# WC_Adaptor.net
KiCad netlist of a schematic drawn in EAGLE
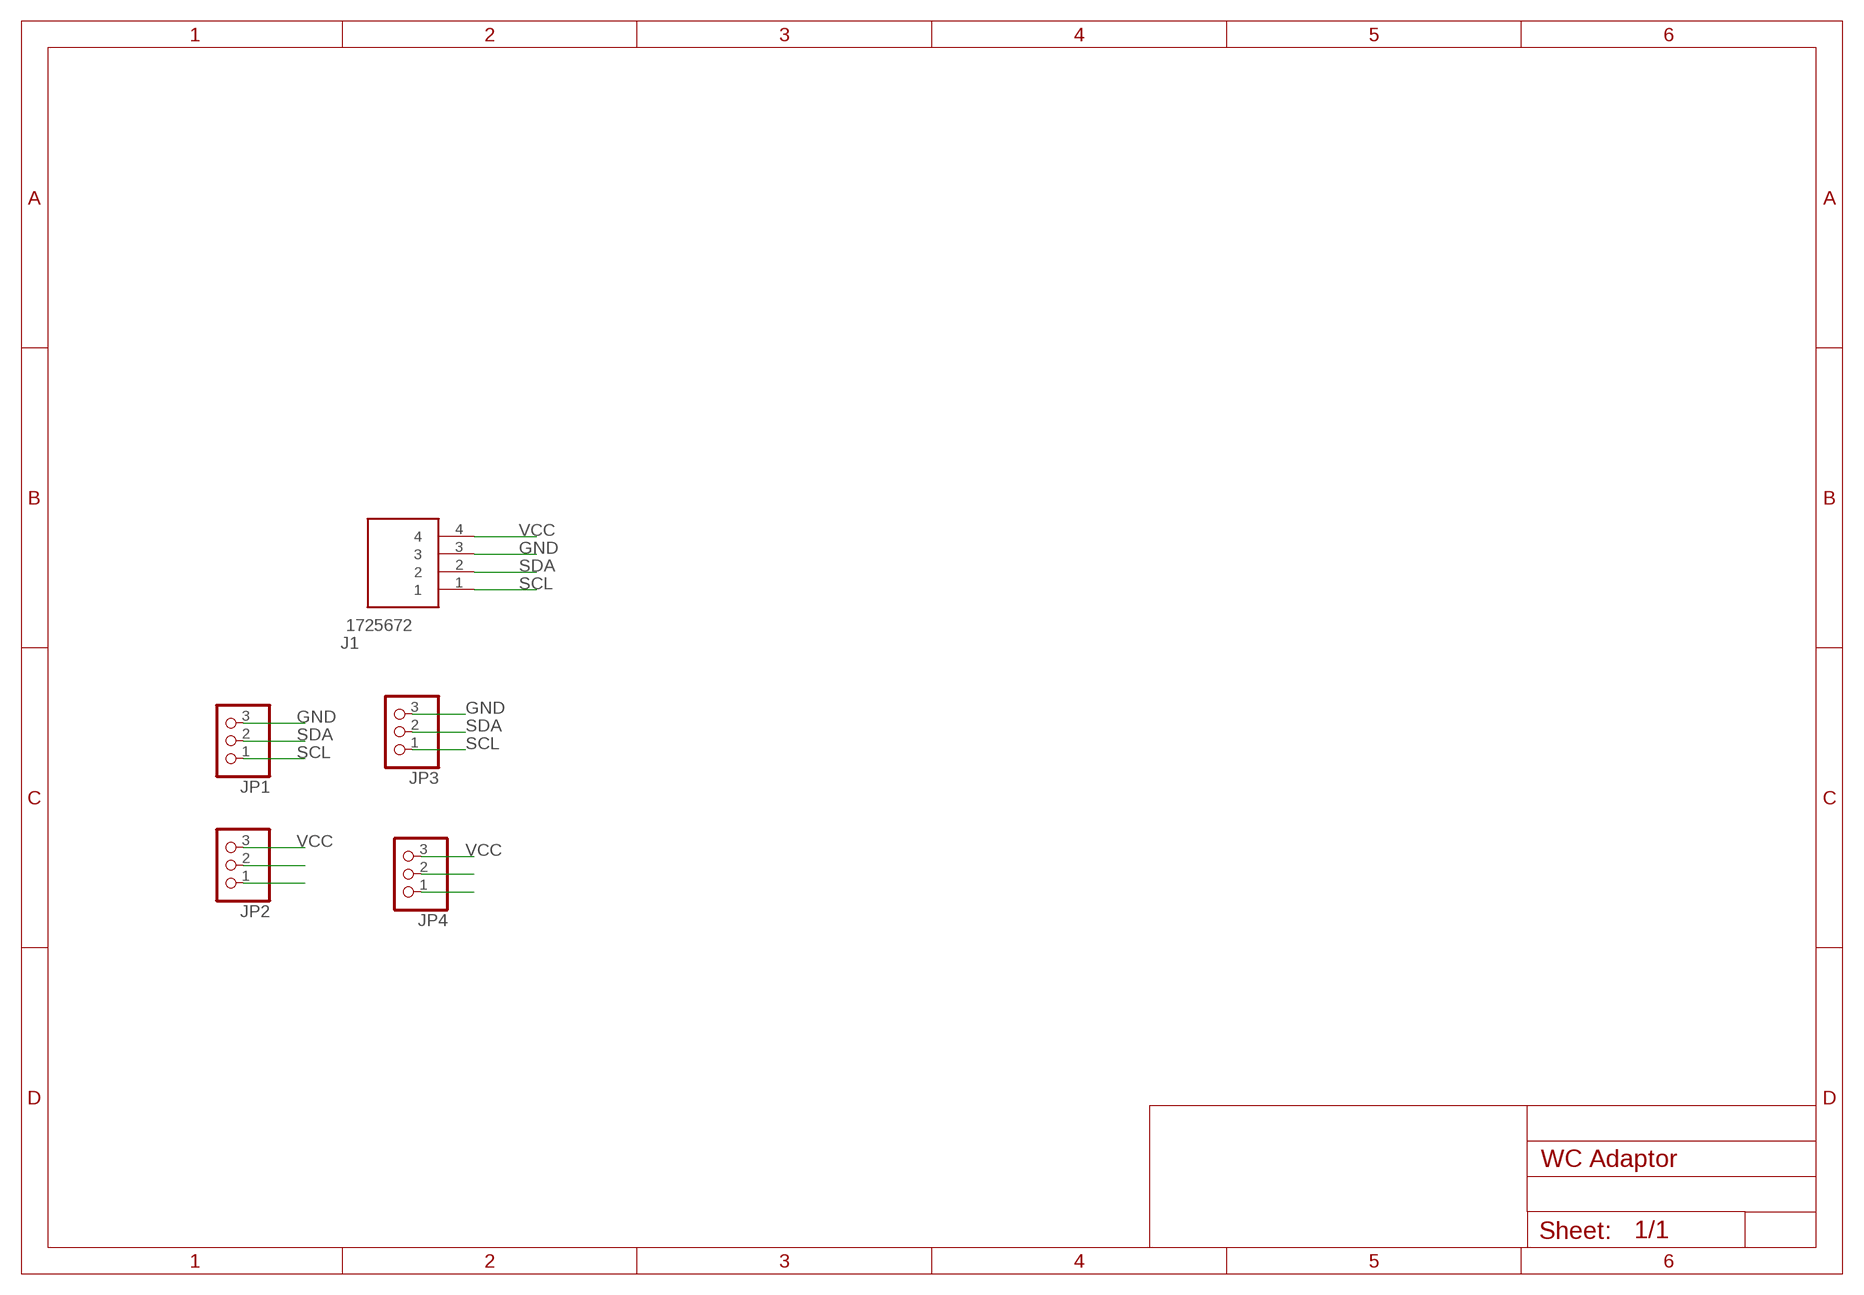
[diagram p0: schematic, sheet 1]

(export (version "E")
  (design (tool "Eeschema 10.0.6"))
  (components
    (comp (ref "J1")
      (value "1725672")
      (footprint "eagle-import:1725672")
      (fields (field (name "MOUSER_PART_NUMBER") "651-1725672"))
      (libsource (lib "eagle-import") (part "1725672"))
    )
    (comp (ref "JP1")
      (value "PINHD-1X3")
      (footprint "eagle-import:1X03")
      (libsource (lib "eagle-import") (part "PINHD-1X3"))
    )
    (comp (ref "JP2")
      (value "PINHD-1X3")
      (footprint "eagle-import:1X03")
      (libsource (lib "eagle-import") (part "PINHD-1X3"))
    )
    (comp (ref "JP3")
      (value "PINHD-1X3")
      (footprint "eagle-import:1X03")
      (libsource (lib "eagle-import") (part "PINHD-1X3"))
    )
    (comp (ref "JP4")
      (value "PINHD-1X3")
      (footprint "eagle-import:1X03")
      (libsource (lib "eagle-import") (part "PINHD-1X3"))
    )
  )
  (nets
    (net (code "1") (name "/GND") (class "Default")
      (node (ref "J1") (pin "3") (pinfunction "3_3") (pintype "bidirectional"))
      (node (ref "JP1") (pin "3") (pinfunction "3_3") (pintype "passive"))
      (node (ref "JP3") (pin "3") (pinfunction "3_3") (pintype "passive"))
    )
    (net (code "2") (name "/SCL") (class "Default")
      (node (ref "J1") (pin "1") (pinfunction "1_1") (pintype "bidirectional"))
      (node (ref "JP1") (pin "1") (pinfunction "1_1") (pintype "passive"))
      (node (ref "JP3") (pin "1") (pinfunction "1_1") (pintype "passive"))
    )
    (net (code "3") (name "/SDA") (class "Default")
      (node (ref "J1") (pin "2") (pinfunction "2_2") (pintype "bidirectional"))
      (node (ref "JP1") (pin "2") (pinfunction "2_2") (pintype "passive"))
      (node (ref "JP3") (pin "2") (pinfunction "2_2") (pintype "passive"))
    )
    (net (code "4") (name "/VCC") (class "Default")
      (node (ref "J1") (pin "4") (pinfunction "4_4") (pintype "bidirectional"))
      (node (ref "JP2") (pin "3") (pinfunction "3_3") (pintype "passive"))
      (node (ref "JP4") (pin "3") (pinfunction "3_3") (pintype "passive"))
    )
    (net (code "5") (name "unconnected-(JP2-Pad1)") (class "Default")
      (node (ref "JP2") (pin "1") (pinfunction "1_1") (pintype "passive"))
    )
    (net (code "6") (name "unconnected-(JP2-Pad2)") (class "Default")
      (node (ref "JP2") (pin "2") (pinfunction "2_2") (pintype "passive"))
    )
    (net (code "7") (name "unconnected-(JP4-Pad1)") (class "Default")
      (node (ref "JP4") (pin "1") (pinfunction "1_1") (pintype "passive"))
    )
    (net (code "8") (name "unconnected-(JP4-Pad2)") (class "Default")
      (node (ref "JP4") (pin "2") (pinfunction "2_2") (pintype "passive"))
    )
  )
)
